# TP_IHM_MAIN.net
KiCad netlist of a schematic drawn in Altium Designer
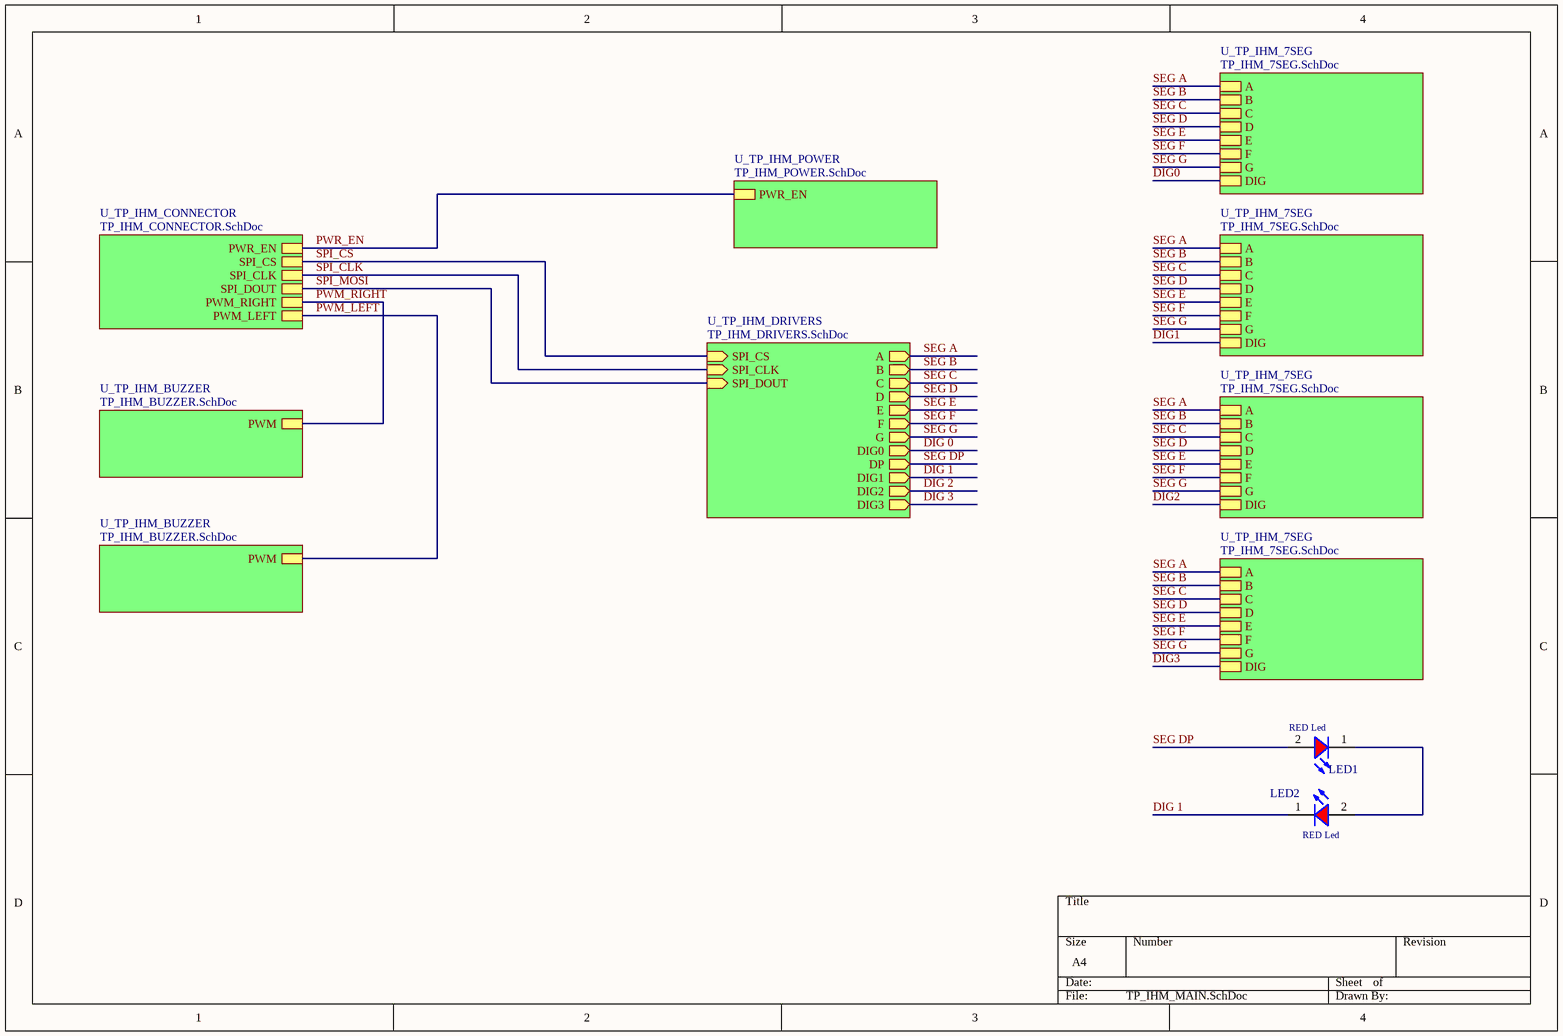
[diagram p0: TP_IHM_MAIN.SchDoc]

(export (version "E")
  (design (tool "Eeschema 10.0.6"))
  (components
    (comp (ref "LED1")
      (value "RED Led")
      (footprint "LED_0603_RED")
      (description "LED RED SMD WE 150060RS750x0")
      (libsource (lib "TpGivenLib") (part "LED_RED_SMD_WE_150060RS750x0"))
    )
    (comp (ref "LED2")
      (value "RED Led")
      (footprint "LED_0603_RED")
      (description "LED RED SMD WE 150060RS750x0")
      (libsource (lib "TpGivenLib") (part "LED_RED_SMD_WE_150060RS750x0"))
    )
  )
  (nets
    (net (code "2") (name "/DIG 1") (class "Default")
      (node (ref "LED2") (pin "1") (pinfunction "K_1") (pintype "passive"))
    )
    (net (code "16") (name "/SEG DP") (class "Default")
      (node (ref "LED1") (pin "2") (pinfunction "A_2") (pintype "passive"))
    )
    (net (code "23") (name "Net-(LED1-K)") (class "Default")
      (node (ref "LED1") (pin "1") (pinfunction "K_1") (pintype "passive"))
      (node (ref "LED2") (pin "2") (pinfunction "A_2") (pintype "passive"))
    )
  )
)
